# Qwiic_Switch.net
KiCad netlist of a schematic drawn in EAGLE
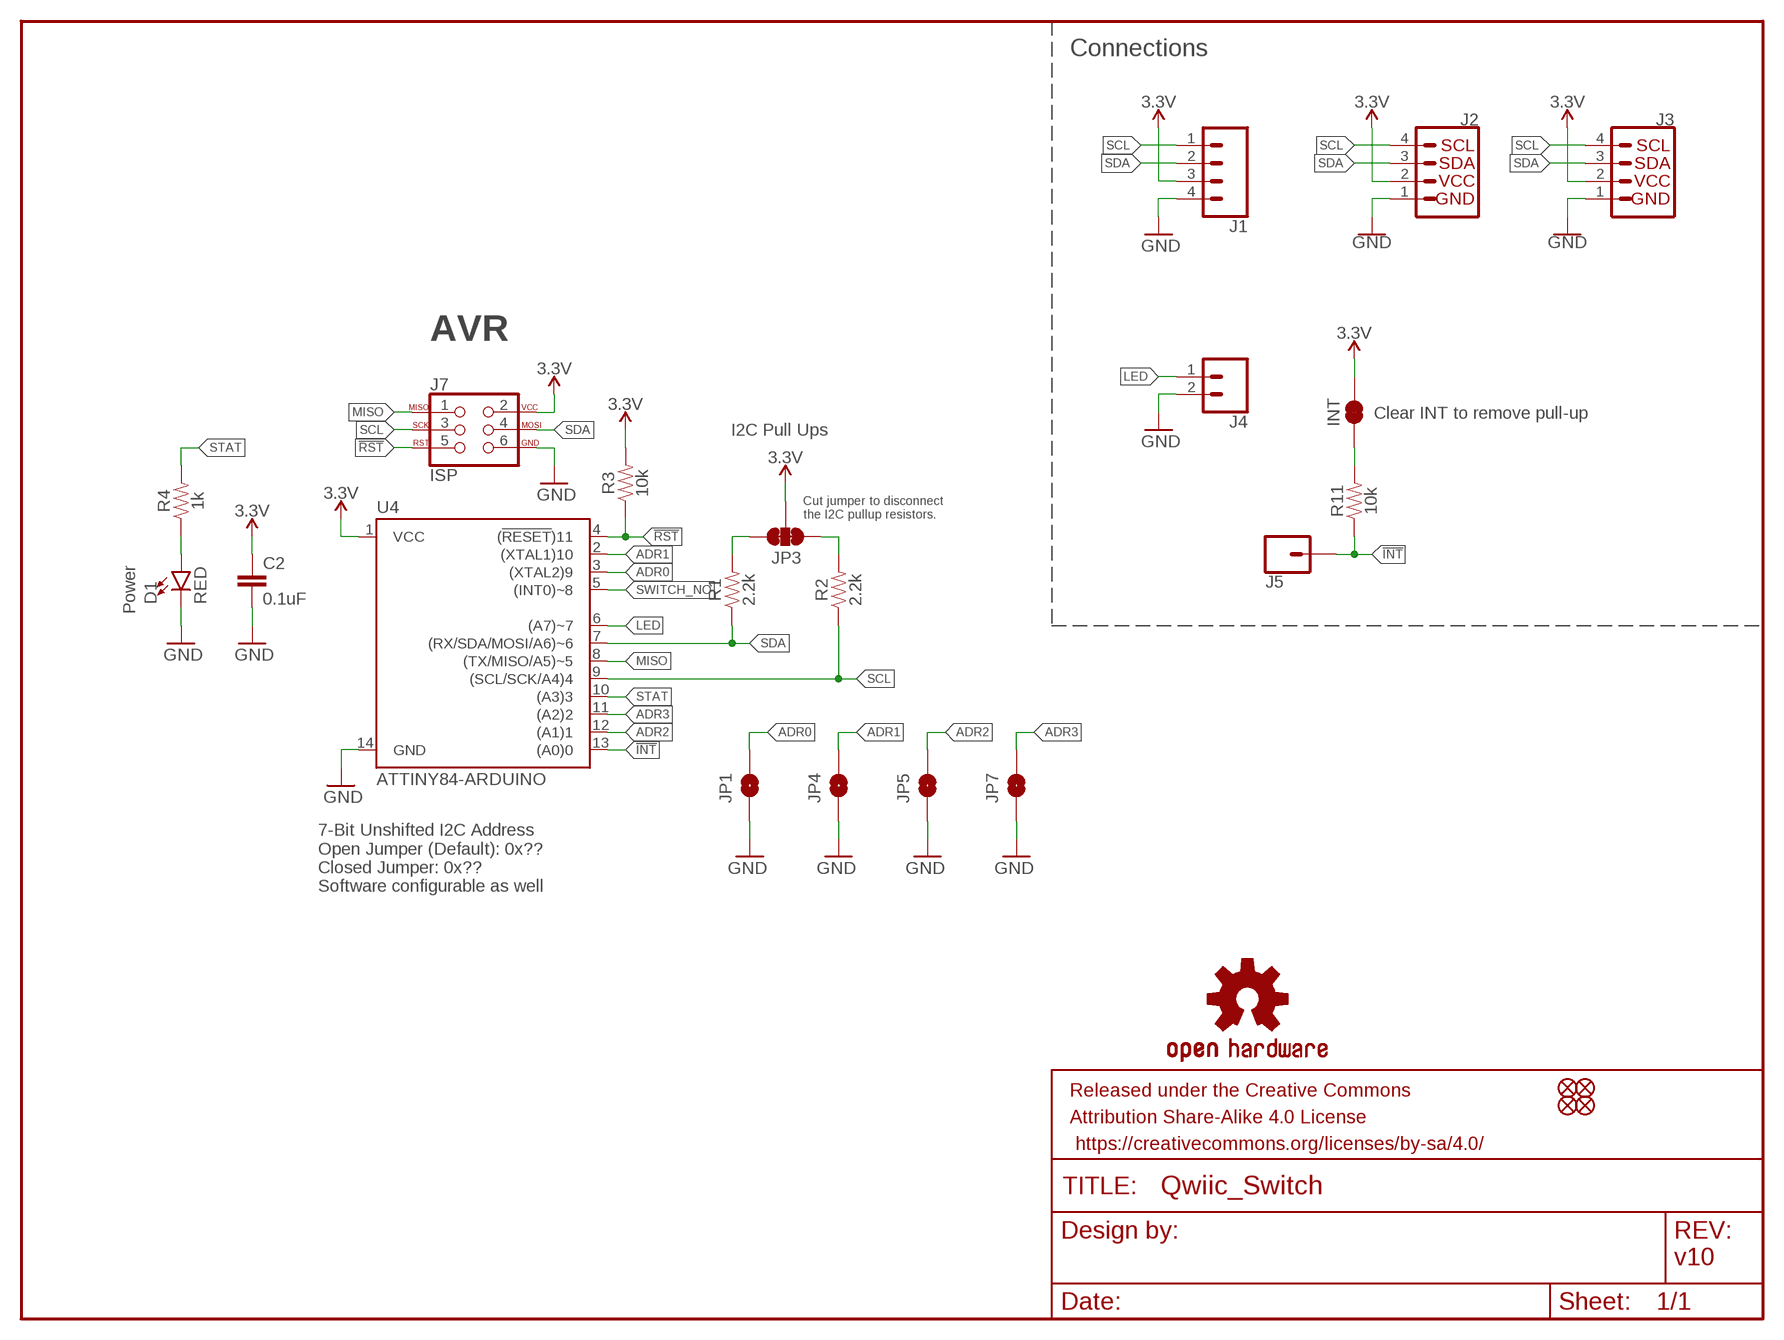
[diagram p0: schematic, sheet 1]

(export (version "E")
  (design (tool "Eeschema 10.0.6"))
  (components
    (comp (ref "C2")
      (value "0.1uF")
      (footprint "eagle-import:0603")
      (libsource (lib "eagle-import") (part "0.1UF-0603-25V-(+80/-20%)"))
    )
    (comp (ref "D1")
      (value "RED")
      (footprint "eagle-import:LED-0603")
      (libsource (lib "eagle-import") (part "LED-RED0603"))
    )
    (comp (ref "FRAME1")
      (value "FRAME-LETTER")
      (footprint "eagle-import:CREATIVE_COMMONS")
      (libsource (lib "eagle-import") (part "FRAME-LETTER"))
    )
    (comp (ref "INT")
      (value "JUMPER-SMT_2_NC_TRACE_SILK")
      (footprint "eagle-import:SMT-JUMPER_2_NC_TRACE_SILK")
      (libsource (lib "eagle-import") (part "JUMPER-SMT_2_NC_TRACE_SILK"))
    )
    (comp (ref "J1")
      (value "CONN_041X04_NO_SILK")
      (footprint "eagle-import:1X04_NO_SILK")
      (libsource (lib "eagle-import") (part "CONN_041X04_NO_SILK"))
    )
    (comp (ref "J2")
      (value "QWIIC_CONNECTORJS-1MM")
      (footprint "eagle-import:JST04_1MM_RA")
      (libsource (lib "eagle-import") (part "QWIIC_CONNECTORJS-1MM"))
    )
    (comp (ref "J3")
      (value "QWIIC_CONNECTORJS-1MM")
      (footprint "eagle-import:JST04_1MM_RA")
      (libsource (lib "eagle-import") (part "QWIIC_CONNECTORJS-1MM"))
    )
    (comp (ref "J4")
      (value "CONN_021X02_NO_SILK")
      (footprint "eagle-import:1X02_NO_SILK")
      (libsource (lib "eagle-import") (part "CONN_021X02_NO_SILK"))
    )
    (comp (ref "J5")
      (value "CONN_01PTH_NO_SILK_YES_STOP")
      (footprint "eagle-import:1X01_NO_SILK")
      (libsource (lib "eagle-import") (part "CONN_01PTH_NO_SILK_YES_STOP"))
    )
    (comp (ref "J7")
      (value "ISP")
      (footprint "eagle-import:2X3_TEST_POINTS")
      (libsource (lib "eagle-import") (part "AVR_SPI_PROG_3X2TESTPOINTS"))
    )
    (comp (ref "JP1")
      (value "JUMPER-SMT_2_NO_SILK")
      (footprint "eagle-import:SMT-JUMPER_2_NO_SILK")
      (libsource (lib "eagle-import") (part "JUMPER-SMT_2_NO_SILK"))
    )
    (comp (ref "JP2")
      (value "FIDUCIALUFIDUCIAL")
      (footprint "eagle-import:MICRO-FIDUCIAL")
      (libsource (lib "eagle-import") (part "FIDUCIALUFIDUCIAL"))
    )
    (comp (ref "JP3")
      (value "JUMPER-SMT_3_2-NC_TRACE_SILK")
      (footprint "eagle-import:SMT-JUMPER_3_2-NC_TRACE_SILK")
      (libsource (lib "eagle-import") (part "JUMPER-SMT_3_2-NC_TRACE_SILK"))
    )
    (comp (ref "JP4")
      (value "JUMPER-SMT_2_NO_SILK")
      (footprint "eagle-import:SMT-JUMPER_2_NO_SILK")
      (libsource (lib "eagle-import") (part "JUMPER-SMT_2_NO_SILK"))
    )
    (comp (ref "JP5")
      (value "JUMPER-SMT_2_NO_SILK")
      (footprint "eagle-import:SMT-JUMPER_2_NO_SILK")
      (libsource (lib "eagle-import") (part "JUMPER-SMT_2_NO_SILK"))
    )
    (comp (ref "JP6")
      (value "FIDUCIALUFIDUCIAL")
      (footprint "eagle-import:MICRO-FIDUCIAL")
      (libsource (lib "eagle-import") (part "FIDUCIALUFIDUCIAL"))
    )
    (comp (ref "JP7")
      (value "JUMPER-SMT_2_NO_SILK")
      (footprint "eagle-import:SMT-JUMPER_2_NO_SILK")
      (libsource (lib "eagle-import") (part "JUMPER-SMT_2_NO_SILK"))
    )
    (comp (ref "JP8")
      (value "FIDUCIALUFIDUCIAL")
      (footprint "eagle-import:MICRO-FIDUCIAL")
      (libsource (lib "eagle-import") (part "FIDUCIALUFIDUCIAL"))
    )
    (comp (ref "JP9")
      (value "FIDUCIALUFIDUCIAL")
      (footprint "eagle-import:MICRO-FIDUCIAL")
      (libsource (lib "eagle-import") (part "FIDUCIALUFIDUCIAL"))
    )
    (comp (ref "LOGO1")
      (value "OSHW-LOGOMINI")
      (footprint "eagle-import:OSHW-LOGO-MINI")
      (libsource (lib "eagle-import") (part "OSHW-LOGOMINI"))
    )
    (comp (ref "R1")
      (value "2.2k")
      (footprint "eagle-import:0603")
      (libsource (lib "eagle-import") (part "2.2KOHM-0603-1/10W-1%"))
    )
    (comp (ref "R2")
      (value "2.2k")
      (footprint "eagle-import:0603")
      (libsource (lib "eagle-import") (part "2.2KOHM-0603-1/10W-1%"))
    )
    (comp (ref "R3")
      (value "10k")
      (footprint "eagle-import:0603")
      (libsource (lib "eagle-import") (part "10KOHM-0603-1/10W-1%"))
    )
    (comp (ref "R4")
      (value "1k")
      (footprint "eagle-import:0603")
      (libsource (lib "eagle-import") (part "1KOHM-0603-1/10W-1%"))
    )
    (comp (ref "R11")
      (value "10k")
      (footprint "eagle-import:0603")
      (libsource (lib "eagle-import") (part "10KOHM-0603-1/10W-1%"))
    )
    (comp (ref "U4")
      (value "ATTINY84-ARDUINO")
      (footprint "eagle-import:SO14")
      (libsource (lib "eagle-import") (part "ATTINY84-ARDUINO"))
    )
  )
  (nets
    (net (code "1") (name "/~{INT}") (class "Default")
      (node (ref "J5") (pin "1") (pinfunction "1_1") (pintype "passive"))
      (node (ref "R11") (pin "1") (pinfunction "1_1") (pintype "passive"))
      (node (ref "U4") (pin "13") (pinfunction "(A0)0_13") (pintype "bidirectional"))
    )
    (net (code "2") (name "/~{RST}") (class "Default")
      (node (ref "J7") (pin "5") (pinfunction "5_5") (pintype "passive"))
      (node (ref "R3") (pin "1") (pinfunction "1_1") (pintype "passive"))
      (node (ref "U4") (pin "4") (pinfunction "(~{RESET})11_4") (pintype "bidirectional"))
    )
    (net (code "3") (name "3.3V") (class "Default")
      (node (ref "C2") (pin "1") (pinfunction "1_1") (pintype "passive"))
      (node (ref "INT") (pin "2") (pinfunction "2_2") (pintype "passive"))
      (node (ref "J1") (pin "3") (pinfunction "3_3") (pintype "passive"))
      (node (ref "J2") (pin "2") (pinfunction "2_2") (pintype "power_in"))
      (node (ref "J3") (pin "2") (pinfunction "2_2") (pintype "power_in"))
      (node (ref "J7") (pin "2") (pinfunction "2_2") (pintype "passive"))
      (node (ref "JP3") (pin "2") (pinfunction "2_2") (pintype "passive"))
      (node (ref "R3") (pin "2") (pinfunction "2_2") (pintype "passive"))
      (node (ref "U4") (pin "1") (pinfunction "VCC_1") (pintype "bidirectional"))
    )
    (net (code "4") (name "ADR0") (class "Default")
      (node (ref "JP1") (pin "2") (pinfunction "2_2") (pintype "passive"))
      (node (ref "U4") (pin "3") (pinfunction "(XTAL2)9_3") (pintype "bidirectional"))
    )
    (net (code "5") (name "ADR1") (class "Default")
      (node (ref "JP4") (pin "2") (pinfunction "2_2") (pintype "passive"))
      (node (ref "U4") (pin "2") (pinfunction "(XTAL1)10_2") (pintype "bidirectional"))
    )
    (net (code "6") (name "ADR2") (class "Default")
      (node (ref "JP5") (pin "2") (pinfunction "2_2") (pintype "passive"))
      (node (ref "U4") (pin "12") (pinfunction "(A1)1_12") (pintype "bidirectional"))
    )
    (net (code "7") (name "ADR3") (class "Default")
      (node (ref "JP7") (pin "2") (pinfunction "2_2") (pintype "passive"))
      (node (ref "U4") (pin "11") (pinfunction "(A2)2_11") (pintype "bidirectional"))
    )
    (net (code "8") (name "GND") (class "Default")
      (node (ref "C2") (pin "2") (pinfunction "2_2") (pintype "passive"))
      (node (ref "D1") (pin "C") (pinfunction "C_C") (pintype "passive"))
      (node (ref "J1") (pin "4") (pinfunction "4_4") (pintype "passive"))
      (node (ref "J2") (pin "1") (pinfunction "1_1") (pintype "power_in"))
      (node (ref "J3") (pin "1") (pinfunction "1_1") (pintype "power_in"))
      (node (ref "J4") (pin "2") (pinfunction "2_2") (pintype "passive"))
      (node (ref "J7") (pin "6") (pinfunction "6_6") (pintype "passive"))
      (node (ref "JP1") (pin "1") (pinfunction "1_1") (pintype "passive"))
      (node (ref "JP4") (pin "1") (pinfunction "1_1") (pintype "passive"))
      (node (ref "JP5") (pin "1") (pinfunction "1_1") (pintype "passive"))
      (node (ref "JP7") (pin "1") (pinfunction "1_1") (pintype "passive"))
      (node (ref "U4") (pin "14") (pinfunction "GND_14") (pintype "bidirectional"))
    )
    (net (code "9") (name "LED") (class "Default")
      (node (ref "J4") (pin "1") (pinfunction "1_1") (pintype "passive"))
      (node (ref "U4") (pin "6") (pinfunction "(A7)~{7}_6") (pintype "bidirectional"))
    )
    (net (code "10") (name "MISO") (class "Default")
      (node (ref "J7") (pin "1") (pinfunction "1_1") (pintype "passive"))
      (node (ref "U4") (pin "8") (pinfunction "(TX/MISO/A5)~{5}_8") (pintype "bidirectional"))
    )
    (net (code "11") (name "Net-(D1-PadA)") (class "Default")
      (node (ref "D1") (pin "A") (pinfunction "A_A") (pintype "passive"))
      (node (ref "R4") (pin "1") (pinfunction "1_1") (pintype "passive"))
    )
    (net (code "12") (name "Net-(INT-Pad1)") (class "Default")
      (node (ref "INT") (pin "1") (pinfunction "1_1") (pintype "passive"))
      (node (ref "R11") (pin "2") (pinfunction "2_2") (pintype "passive"))
    )
    (net (code "13") (name "Net-(JP3-Pad1)") (class "Default")
      (node (ref "JP3") (pin "1") (pinfunction "1_1") (pintype "passive"))
      (node (ref "R2") (pin "2") (pinfunction "2_2") (pintype "passive"))
    )
    (net (code "14") (name "Net-(JP3-Pad3)") (class "Default")
      (node (ref "JP3") (pin "3") (pinfunction "3_3") (pintype "passive"))
      (node (ref "R1") (pin "2") (pinfunction "2_2") (pintype "passive"))
    )
    (net (code "15") (name "SCL") (class "Default")
      (node (ref "J1") (pin "1") (pinfunction "1_1") (pintype "passive"))
      (node (ref "J2") (pin "4") (pinfunction "4_4") (pintype "passive"))
      (node (ref "J3") (pin "4") (pinfunction "4_4") (pintype "passive"))
      (node (ref "J7") (pin "3") (pinfunction "3_3") (pintype "passive"))
      (node (ref "R2") (pin "1") (pinfunction "1_1") (pintype "passive"))
      (node (ref "U4") (pin "9") (pinfunction "(SCL/SCK/A4)4_9") (pintype "bidirectional"))
    )
    (net (code "16") (name "SDA") (class "Default")
      (node (ref "J1") (pin "2") (pinfunction "2_2") (pintype "passive"))
      (node (ref "J2") (pin "3") (pinfunction "3_3") (pintype "passive"))
      (node (ref "J3") (pin "3") (pinfunction "3_3") (pintype "passive"))
      (node (ref "J7") (pin "4") (pinfunction "4_4") (pintype "passive"))
      (node (ref "R1") (pin "1") (pinfunction "1_1") (pintype "passive"))
      (node (ref "U4") (pin "7") (pinfunction "(RX/SDA/MOSI/A6)~{6}_7") (pintype "bidirectional"))
    )
    (net (code "17") (name "STAT") (class "Default")
      (node (ref "R4") (pin "2") (pinfunction "2_2") (pintype "passive"))
      (node (ref "U4") (pin "10") (pinfunction "(A3)3_10") (pintype "bidirectional"))
    )
    (net (code "18") (name "SWITCH_NO") (class "Default")
      (node (ref "U4") (pin "5") (pinfunction "(INT0)~{8}_5") (pintype "bidirectional"))
    )
  )
)
